# Schematic_Open-Book.net
KiCad netlist of a schematic drawn in EAGLE
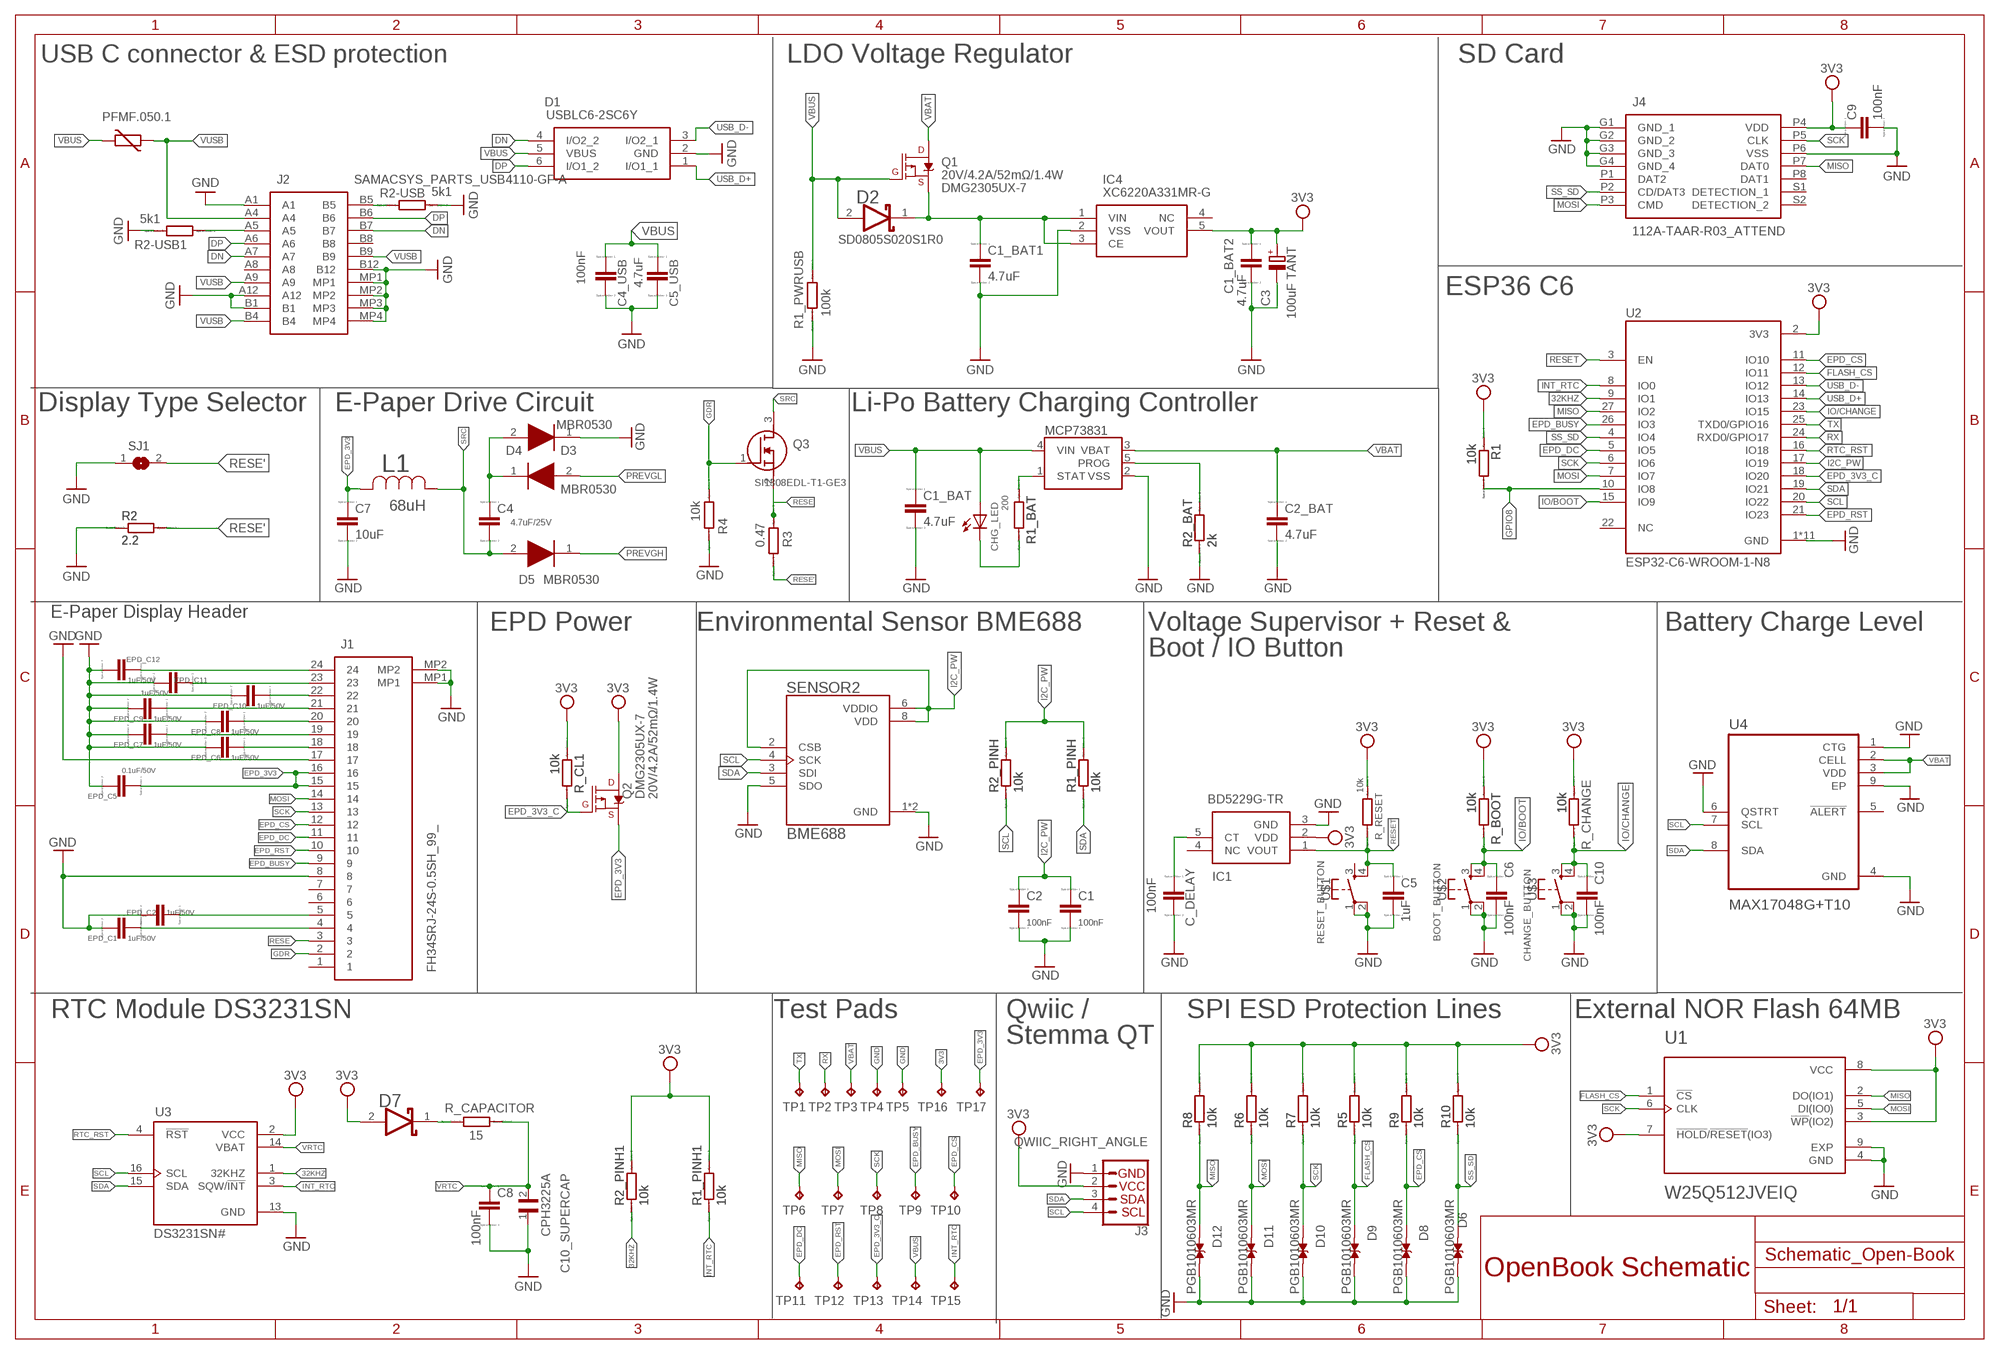
[diagram p0: schematic, sheet 1]

(export (version "E")
  (design (tool "Eeschema 10.0.6"))
  (components
    (comp (ref "C1")
      (value "100nF")
      (footprint "eagle-import:ESP32_WROVER_EAGLE-LTSPICE_C0402")
      (libsource (lib "eagle-import") (part "ESP32_WROVER_EAGLE-LTSPICE_CC0402"))
    )
    (comp (ref "C1_BAT")
      (value "4.7uF")
      (footprint "eagle-import:ESP32_WROVER_EAGLE-LTSPICE_C0402")
      (libsource (lib "eagle-import") (part "ESP32_WROVER_EAGLE-LTSPICE_CC0402"))
    )
    (comp (ref "C1_BAT1")
      (value "4.7uF")
      (footprint "eagle-import:ESP32_WROVER_EAGLE-LTSPICE_C0402")
      (libsource (lib "eagle-import") (part "ESP32_WROVER_EAGLE-LTSPICE_CC0402"))
    )
    (comp (ref "C1_BAT2")
      (value "4.7uF")
      (footprint "eagle-import:ESP32_WROVER_EAGLE-LTSPICE_C0402")
      (libsource (lib "eagle-import") (part "ESP32_WROVER_EAGLE-LTSPICE_CC0402"))
    )
    (comp (ref "C2")
      (value "100nF")
      (footprint "eagle-import:ESP32_WROVER_EAGLE-LTSPICE_C0402")
      (libsource (lib "eagle-import") (part "ESP32_WROVER_EAGLE-LTSPICE_CC0402"))
    )
    (comp (ref "C2_BAT")
      (value "4.7uF")
      (footprint "eagle-import:ESP32_WROVER_EAGLE-LTSPICE_C0402")
      (libsource (lib "eagle-import") (part "ESP32_WROVER_EAGLE-LTSPICE_CC0402"))
    )
    (comp (ref "C3")
      (value "100uF TANT")
      (footprint "eagle-import:RCL_CT3528")
      (libsource (lib "eagle-import") (part "RCL_CPOL-EUCT3528"))
    )
    (comp (ref "C4")
      (value "4.7uF/25V")
      (footprint "eagle-import:ESP32_WROVER_EAGLE-LTSPICE_C0402")
      (libsource (lib "eagle-import") (part "ESP32_WROVER_EAGLE-LTSPICE_CC0402"))
    )
    (comp (ref "C4_USB")
      (value "100nF")
      (footprint "eagle-import:EAGLE-LTSPICE_C0402")
      (libsource (lib "eagle-import") (part "EAGLE-LTSPICE_CC0402"))
    )
    (comp (ref "C5")
      (value "1uF")
      (footprint "eagle-import:ESP32_WROVER_EAGLE-LTSPICE_C0402")
      (libsource (lib "eagle-import") (part "ESP32_WROVER_EAGLE-LTSPICE_CC0402"))
    )
    (comp (ref "C5_USB")
      (value "4.7uF")
      (footprint "eagle-import:EAGLE-LTSPICE_C0402")
      (libsource (lib "eagle-import") (part "EAGLE-LTSPICE_CC0402"))
    )
    (comp (ref "C6")
      (value "100nF")
      (footprint "eagle-import:ESP32_WROVER_EAGLE-LTSPICE_C0402")
      (libsource (lib "eagle-import") (part "ESP32_WROVER_EAGLE-LTSPICE_CC0402"))
    )
    (comp (ref "C7")
      (value "10uF")
      (footprint "eagle-import:ESP32_WROVER_EAGLE-LTSPICE_C0402")
      (libsource (lib "eagle-import") (part "ESP32_WROVER_EAGLE-LTSPICE_CC0402"))
    )
    (comp (ref "C8")
      (value "100nF")
      (footprint "eagle-import:ESP32_WROVER_EAGLE-LTSPICE_C0402")
      (libsource (lib "eagle-import") (part "ESP32_WROVER_EAGLE-LTSPICE_CC0402"))
    )
    (comp (ref "C9")
      (value "100nF")
      (footprint "eagle-import:ESP32_WROVER_EAGLE-LTSPICE_C0402")
      (libsource (lib "eagle-import") (part "ESP32_WROVER_EAGLE-LTSPICE_CC0402"))
    )
    (comp (ref "C10")
      (value "100nF")
      (footprint "eagle-import:ESP32_WROVER_EAGLE-LTSPICE_C0402")
      (libsource (lib "eagle-import") (part "ESP32_WROVER_EAGLE-LTSPICE_CC0402"))
    )
    (comp (ref "C10_SUPERCAP")
      (value "CPH3225A")
      (footprint "eagle-import:CAPCP3225X100N")
      (fields (field (name "MF") "Seiko Instruments"))
      (libsource (lib "eagle-import") (part "CPH3225A"))
    )
    (comp (ref "CHG_LED")
      (value "ADAFRUIT_LEDCHIP-LED0603")
      (footprint "eagle-import:ADAFRUIT_CHIP-LED0603")
      (libsource (lib "eagle-import") (part "ADAFRUIT_LEDCHIP-LED0603"))
    )
    (comp (ref "C_DELAY")
      (value "100nF")
      (footprint "eagle-import:ESP32_WROVER_EAGLE-LTSPICE_C0402")
      (libsource (lib "eagle-import") (part "ESP32_WROVER_EAGLE-LTSPICE_CC0402"))
    )
    (comp (ref "D1")
      (value "USBLC6-2SC6Y")
      (footprint "eagle-import:SOT95P280X145-6N")
      (fields (field (name "MF") "STMicroelectronics"))
      (libsource (lib "eagle-import") (part "USBLC6-2SC6Y"))
    )
    (comp (ref "D2")
      (value "ESP32_WROVER_AVX---SD0805S020S1R0_AVX_SD0805S020S1R0_0_0AVX_SD0805S020S1R0_0_0")
      (footprint "eagle-import:ESP32_WROVER_AVX---SD0805S020S1R0_AVX_SD0805S020S1R0_0")
      (fields
        (field (name "DIGIKEY_PART_NUMBER") "478-7800-1-ND")
        (field (name "MF") "AVX")
        (field (name "MOUSER_PART_NUMBER") "581-SD0805S020S1R0")
      )
      (libsource (lib "eagle-import") (part "ESP32_WROVER_AVX---SD0805S020S1R0_AVX_SD0805S020S1R0_0_0AVX_SD0805S020S1R0_0_0"))
    )
    (comp (ref "D3")
      (value "MBR0530")
      (footprint "eagle-import:SOD3716X135N")
      (fields (field (name "MF") "ON Semiconductor"))
      (libsource (lib "eagle-import") (part "MBR0530"))
    )
    (comp (ref "D4")
      (value "MBR0530")
      (footprint "eagle-import:SOD3716X135N")
      (fields (field (name "MF") "ON Semiconductor"))
      (libsource (lib "eagle-import") (part "MBR0530"))
    )
    (comp (ref "D5")
      (value "MBR0530")
      (footprint "eagle-import:SOD3716X135N")
      (fields (field (name "MF") "ON Semiconductor"))
      (libsource (lib "eagle-import") (part "MBR0530"))
    )
    (comp (ref "D6")
      (value "PGB1010603MR")
      (footprint "eagle-import:DIOC1608X36N")
      (fields (field (name "MF") "Littelfuse Inc."))
      (libsource (lib "eagle-import") (part "PGB1010603MR"))
    )
    (comp (ref "D7")
      (value "ESP32_WROVER_AVX---SD0805S020S1R0_AVX_SD0805S020S1R0_0_0AVX_SD0805S020S1R0_0_0")
      (footprint "eagle-import:ESP32_WROVER_AVX---SD0805S020S1R0_AVX_SD0805S020S1R0_0")
      (fields
        (field (name "DIGIKEY_PART_NUMBER") "478-7800-1-ND")
        (field (name "MF") "AVX")
        (field (name "MOUSER_PART_NUMBER") "581-SD0805S020S1R0")
      )
      (libsource (lib "eagle-import") (part "ESP32_WROVER_AVX---SD0805S020S1R0_AVX_SD0805S020S1R0_0_0AVX_SD0805S020S1R0_0_0"))
    )
    (comp (ref "D8")
      (value "PGB1010603MR")
      (footprint "eagle-import:DIOC1608X36N")
      (fields (field (name "MF") "Littelfuse Inc."))
      (libsource (lib "eagle-import") (part "PGB1010603MR"))
    )
    (comp (ref "D9")
      (value "PGB1010603MR")
      (footprint "eagle-import:DIOC1608X36N")
      (fields (field (name "MF") "Littelfuse Inc."))
      (libsource (lib "eagle-import") (part "PGB1010603MR"))
    )
    (comp (ref "D10")
      (value "PGB1010603MR")
      (footprint "eagle-import:DIOC1608X36N")
      (fields (field (name "MF") "Littelfuse Inc."))
      (libsource (lib "eagle-import") (part "PGB1010603MR"))
    )
    (comp (ref "D11")
      (value "PGB1010603MR")
      (footprint "eagle-import:DIOC1608X36N")
      (fields (field (name "MF") "Littelfuse Inc."))
      (libsource (lib "eagle-import") (part "PGB1010603MR"))
    )
    (comp (ref "D12")
      (value "PGB1010603MR")
      (footprint "eagle-import:DIOC1608X36N")
      (fields (field (name "MF") "Littelfuse Inc."))
      (libsource (lib "eagle-import") (part "PGB1010603MR"))
    )
    (comp (ref "EPD_C1")
      (value "1uF/50V")
      (footprint "eagle-import:ESP32_WROVER_EAGLE-LTSPICE_C0402")
      (libsource (lib "eagle-import") (part "ESP32_WROVER_EAGLE-LTSPICE_CC0402"))
    )
    (comp (ref "EPD_C2")
      (value "1uF/50V")
      (footprint "eagle-import:ESP32_WROVER_EAGLE-LTSPICE_C0402")
      (libsource (lib "eagle-import") (part "ESP32_WROVER_EAGLE-LTSPICE_CC0402"))
    )
    (comp (ref "EPD_C5")
      (value "0.1uF/50V")
      (footprint "eagle-import:EAGLE-LTSPICE_C0402")
      (libsource (lib "eagle-import") (part "EAGLE-LTSPICE_CC0402"))
    )
    (comp (ref "EPD_C6")
      (value "1uF/50V")
      (footprint "eagle-import:EAGLE-LTSPICE_C0402")
      (libsource (lib "eagle-import") (part "EAGLE-LTSPICE_CC0402"))
    )
    (comp (ref "EPD_C7")
      (value "1uF/50V")
      (footprint "eagle-import:EAGLE-LTSPICE_C0402")
      (libsource (lib "eagle-import") (part "EAGLE-LTSPICE_CC0402"))
    )
    (comp (ref "EPD_C8")
      (value "1uF/50V")
      (footprint "eagle-import:EAGLE-LTSPICE_C0402")
      (libsource (lib "eagle-import") (part "EAGLE-LTSPICE_CC0402"))
    )
    (comp (ref "EPD_C9")
      (value "1uF/50V")
      (footprint "eagle-import:EAGLE-LTSPICE_C0402")
      (libsource (lib "eagle-import") (part "EAGLE-LTSPICE_CC0402"))
    )
    (comp (ref "EPD_C10")
      (value "1uF/50V")
      (footprint "eagle-import:EAGLE-LTSPICE_C0402")
      (libsource (lib "eagle-import") (part "EAGLE-LTSPICE_CC0402"))
    )
    (comp (ref "EPD_C11")
      (value "1uF/50V")
      (footprint "eagle-import:EAGLE-LTSPICE_C0402")
      (libsource (lib "eagle-import") (part "EAGLE-LTSPICE_CC0402"))
    )
    (comp (ref "EPD_C12")
      (value "1uF/50V")
      (footprint "eagle-import:EAGLE-LTSPICE_C0402")
      (libsource (lib "eagle-import") (part "EAGLE-LTSPICE_CC0402"))
    )
    (comp (ref "IC1")
      (value "BD5229G-TR")
      (footprint "eagle-import:SOT95P280X125-5N")
      (fields (field (name "MOUSER_PART_NUMBER") "755-BD5229G-TR"))
      (libsource (lib "eagle-import") (part "BD5229G-TR"))
    )
    (comp (ref "IC4")
      (value "XC6220A331MR-G")
      (footprint "eagle-import:SOT95P280X120-5N")
      (fields (field (name "MOUSER_PART_NUMBER") "865-XC6220A331MR-G"))
      (libsource (lib "eagle-import") (part "XC6220A331MR-G"))
    )
    (comp (ref "J1")
      (value "FH34SRJ-24S-0.5SH_99_")
      (footprint "eagle-import:FH34SRJ24S05SH99")
      (fields
        (field (name "MANUFACTURER_PART_NUMBER") "FH34SRJ-24S-0.5SH(99)")
        (field (name "MOUSER_PART_NUMBER") "798-FH34SRJ24S05SH99")
      )
      (libsource (lib "eagle-import") (part "FH34SRJ-24S-0.5SH_99_"))
    )
    (comp (ref "J2")
      (value "SAMACSYS_PARTS_USB4110-GF-A")
      (footprint "eagle-import:SAMACSYS_PARTS_USB4110GFA")
      (fields
        (field (name "MANUFACTURER_PART_NUMBER") "USB4110-GF-A")
        (field (name "MOUSER_PART_NUMBER") "640-USB4110-GF-A")
      )
      (libsource (lib "eagle-import") (part "SAMACSYS_PARTS_USB4110-GF-A"))
    )
    (comp (ref "J3")
      (value "QWIIC_RIGHT_ANGLE")
      (footprint "eagle-import:JST04_1MM_RA")
      (libsource (lib "eagle-import") (part "QWIIC_CONNECTORJS-1MM"))
    )
    (comp (ref "J4")
      (value "112A-TAAR-R03_ATTEND")
      (footprint "eagle-import:112ATAARR03ATTEND")
      (fields (field (name "MANUFACTURER_PART_NUMBER") "112A-TAAR-R03 ATTEND"))
      (libsource (lib "eagle-import") (part "112A-TAAR-R03_ATTEND"))
    )
    (comp (ref "L1")
      (value "68uH")
      (footprint "eagle-import:IND_4828-WE-TPC_WRE")
      (fields
        (field (name "MANUFACTURER_PART_NUMBER") "744043680")
        (field (name "COPYRIGHT") "Copyright (C) 2024 Ultra Librarian. All rights reserved.")
      )
      (libsource (lib "eagle-import") (part "744043680IND_4828-WE-TPC_WRE"))
    )
    (comp (ref "MCP73831")
      (value "ESP32_WROVER_SPARKFUN-IC-POWER_MCP73831")
      (footprint "eagle-import:ESP32_WROVER_SPARKFUN-IC-POWER_SOT23-5")
      (libsource (lib "eagle-import") (part "ESP32_WROVER_SPARKFUN-IC-POWER_MCP73831"))
    )
    (comp (ref "PFMF.050.1")
      (value "ESP32C6_VARISTORCN1812")
      (footprint "eagle-import:ESP32C6_VARISTOR_CT_CN1812")
      (libsource (lib "eagle-import") (part "ESP32C6_VARISTORCN1812"))
    )
    (comp (ref "Q1")
      (value "20V/4.2A/52mΩ/1.4W")
      (footprint "eagle-import:ESP32_WROVER_SPARKFUN-DISCRETESEMI_SOT23-3")
      (libsource (lib "eagle-import") (part "ESP32_WROVER_SPARKFUN-DISCRETESEMI_MOSFET_PCH-DMG2305UX-7"))
    )
    (comp (ref "Q2")
      (value "20V/4.2A/52mΩ/1.4W")
      (footprint "eagle-import:ESP32_WROVER_SPARKFUN-DISCRETESEMI_SOT23-3")
      (libsource (lib "eagle-import") (part "ESP32_WROVER_SPARKFUN-DISCRETESEMI_MOSFET_PCH-DMG2305UX-7"))
    )
    (comp (ref "Q3")
      (value "SI1308EDL-T1-GE3")
      (footprint "eagle-import:SOT65P210X110-3N")
      (fields (field (name "MF") "Vishay Siliconix"))
      (libsource (lib "eagle-import") (part "SI1308EDL-T1-GE3"))
    )
    (comp (ref "R1")
      (value "10k")
      (footprint "eagle-import:ESP32_WROVER_EAGLE-LTSPICE_R0402")
      (libsource (lib "eagle-import") (part "ESP32_WROVER_EAGLE-LTSPICE_RR0402"))
    )
    (comp (ref "R1_BAT")
      (value "200")
      (footprint "eagle-import:ESP32_WROVER_EAGLE-LTSPICE_R0402")
      (libsource (lib "eagle-import") (part "ESP32_WROVER_EAGLE-LTSPICE_RR0402"))
    )
    (comp (ref "R1_PINH")
      (value "10k")
      (footprint "eagle-import:ESP32_WROVER_EAGLE-LTSPICE_R0402")
      (libsource (lib "eagle-import") (part "ESP32_WROVER_EAGLE-LTSPICE_RR0402"))
    )
    (comp (ref "R1_PINH1")
      (value "10k")
      (footprint "eagle-import:ESP32_WROVER_EAGLE-LTSPICE_R0402")
      (libsource (lib "eagle-import") (part "ESP32_WROVER_EAGLE-LTSPICE_RR0402"))
    )
    (comp (ref "R1_PWRUSB")
      (value "100k")
      (footprint "eagle-import:ESP32_WROVER_EAGLE-LTSPICE_R0402")
      (libsource (lib "eagle-import") (part "ESP32_WROVER_EAGLE-LTSPICE_RR0402"))
    )
    (comp (ref "R2")
      (value "2.2")
      (footprint "eagle-import:ESP32_WROVER_EAGLE-LTSPICE_R0402")
      (libsource (lib "eagle-import") (part "ESP32_WROVER_EAGLE-LTSPICE_RR0402"))
    )
    (comp (ref "R2-USB")
      (value "5k1")
      (footprint "eagle-import:ESP32_WROVER_EAGLE-LTSPICE_R0402")
      (libsource (lib "eagle-import") (part "ESP32_WROVER_EAGLE-LTSPICE_RR0402"))
    )
    (comp (ref "R2-USB1")
      (value "5k1")
      (footprint "eagle-import:ESP32_WROVER_EAGLE-LTSPICE_R0402")
      (libsource (lib "eagle-import") (part "ESP32_WROVER_EAGLE-LTSPICE_RR0402"))
    )
    (comp (ref "R2_BAT")
      (value "2k")
      (footprint "eagle-import:ESP32_WROVER_EAGLE-LTSPICE_R0402")
      (libsource (lib "eagle-import") (part "ESP32_WROVER_EAGLE-LTSPICE_RR0402"))
    )
    (comp (ref "R2_PINH")
      (value "10k")
      (footprint "eagle-import:ESP32_WROVER_EAGLE-LTSPICE_R0402")
      (libsource (lib "eagle-import") (part "ESP32_WROVER_EAGLE-LTSPICE_RR0402"))
    )
    (comp (ref "R2_PINH1")
      (value "10k")
      (footprint "eagle-import:ESP32_WROVER_EAGLE-LTSPICE_R0402")
      (libsource (lib "eagle-import") (part "ESP32_WROVER_EAGLE-LTSPICE_RR0402"))
    )
    (comp (ref "R3")
      (value "0.47")
      (footprint "eagle-import:ESP32_WROVER_EAGLE-LTSPICE_R0402")
      (libsource (lib "eagle-import") (part "ESP32_WROVER_EAGLE-LTSPICE_RR0402"))
    )
    (comp (ref "R4")
      (value "10k")
      (footprint "eagle-import:ESP32_WROVER_EAGLE-LTSPICE_R0402")
      (libsource (lib "eagle-import") (part "ESP32_WROVER_EAGLE-LTSPICE_RR0402"))
    )
    (comp (ref "R5")
      (value "10k")
      (footprint "eagle-import:ESP32_WROVER_EAGLE-LTSPICE_R0402")
      (libsource (lib "eagle-import") (part "ESP32_WROVER_EAGLE-LTSPICE_RR0402"))
    )
    (comp (ref "R6")
      (value "10k")
      (footprint "eagle-import:ESP32_WROVER_EAGLE-LTSPICE_R0402")
      (libsource (lib "eagle-import") (part "ESP32_WROVER_EAGLE-LTSPICE_RR0402"))
    )
    (comp (ref "R7")
      (value "10k")
      (footprint "eagle-import:ESP32_WROVER_EAGLE-LTSPICE_R0402")
      (libsource (lib "eagle-import") (part "ESP32_WROVER_EAGLE-LTSPICE_RR0402"))
    )
    (comp (ref "R8")
      (value "10k")
      (footprint "eagle-import:ESP32_WROVER_EAGLE-LTSPICE_R0402")
      (libsource (lib "eagle-import") (part "ESP32_WROVER_EAGLE-LTSPICE_RR0402"))
    )
    (comp (ref "R9")
      (value "10k")
      (footprint "eagle-import:ESP32_WROVER_EAGLE-LTSPICE_R0402")
      (libsource (lib "eagle-import") (part "ESP32_WROVER_EAGLE-LTSPICE_RR0402"))
    )
    (comp (ref "R10")
      (value "10k")
      (footprint "eagle-import:ESP32_WROVER_EAGLE-LTSPICE_R0402")
      (libsource (lib "eagle-import") (part "ESP32_WROVER_EAGLE-LTSPICE_RR0402"))
    )
    (comp (ref "R_BOOT")
      (value "10k")
      (footprint "eagle-import:ESP32_WROVER_EAGLE-LTSPICE_R0402")
      (libsource (lib "eagle-import") (part "ESP32_WROVER_EAGLE-LTSPICE_RR0402"))
    )
    (comp (ref "R_CAPACITOR")
      (value "15")
      (footprint "eagle-import:ESP32_WROVER_EAGLE-LTSPICE_R0402")
      (libsource (lib "eagle-import") (part "ESP32_WROVER_EAGLE-LTSPICE_RR0402"))
    )
    (comp (ref "R_CHANGE")
      (value "10k")
      (footprint "eagle-import:ESP32_WROVER_EAGLE-LTSPICE_R0402")
      (libsource (lib "eagle-import") (part "ESP32_WROVER_EAGLE-LTSPICE_RR0402"))
    )
    (comp (ref "R_CL1")
      (value "10k")
      (footprint "eagle-import:ESP32_WROVER_EAGLE-LTSPICE_R0402")
      (libsource (lib "eagle-import") (part "ESP32_WROVER_EAGLE-LTSPICE_RR0402"))
    )
    (comp (ref "R_RESET")
      (value "10k")
      (footprint "eagle-import:ESP32_WROVER_EAGLE-LTSPICE_R0402")
      (libsource (lib "eagle-import") (part "ESP32_WROVER_EAGLE-LTSPICE_RR0402"))
    )
    (comp (ref "SENSOR2")
      (value "BME688")
      (footprint "eagle-import:ESP32_WROVER_BME680_PSON80P300X300X100-8N")
      (fields (field (name "MF") "Bosch Sensortec") (field (name "MP") "BME680"))
      (libsource (lib "eagle-import") (part "ESP32_WROVER_BME680_BME680"))
    )
    (comp (ref "SJ1") (value "SJ") (footprint "eagle-import:SJ") (libsource (lib "eagle-import") (part "SJ")))
    (comp (ref "TP1")
      (value "TPTP20R")
      (footprint "eagle-import:TP20R")
      (libsource (lib "eagle-import") (part "TPTP20R"))
    )
    (comp (ref "TP2")
      (value "TPTP20R")
      (footprint "eagle-import:TP20R")
      (libsource (lib "eagle-import") (part "TPTP20R"))
    )
    (comp (ref "TP3")
      (value "TPTP20R")
      (footprint "eagle-import:TP20R")
      (libsource (lib "eagle-import") (part "TPTP20R"))
    )
    (comp (ref "TP4")
      (value "TPTP20R")
      (footprint "eagle-import:TP20R")
      (libsource (lib "eagle-import") (part "TPTP20R"))
    )
    (comp (ref "TP5")
      (value "TPTP20R")
      (footprint "eagle-import:TP20R")
      (libsource (lib "eagle-import") (part "TPTP20R"))
    )
    (comp (ref "TP6")
      (value "TPTP20R")
      (footprint "eagle-import:TP20R")
      (libsource (lib "eagle-import") (part "TPTP20R"))
    )
    (comp (ref "TP7")
      (value "TPTP20R")
      (footprint "eagle-import:TP20R")
      (libsource (lib "eagle-import") (part "TPTP20R"))
    )
    (comp (ref "TP8")
      (value "TPTP20R")
      (footprint "eagle-import:TP20R")
      (libsource (lib "eagle-import") (part "TPTP20R"))
    )
    (comp (ref "TP9")
      (value "TPTP20R")
      (footprint "eagle-import:TP20R")
      (libsource (lib "eagle-import") (part "TPTP20R"))
    )
    (comp (ref "TP10")
      (value "TPTP20R")
      (footprint "eagle-import:TP20R")
      (libsource (lib "eagle-import") (part "TPTP20R"))
    )
    (comp (ref "TP11")
      (value "TPTP20R")
      (footprint "eagle-import:TP20R")
      (libsource (lib "eagle-import") (part "TPTP20R"))
    )
    (comp (ref "TP12")
      (value "TPTP20R")
      (footprint "eagle-import:TP20R")
      (libsource (lib "eagle-import") (part "TPTP20R"))
    )
    (comp (ref "TP13")
      (value "TPTP20R")
      (footprint "eagle-import:TP20R")
      (libsource (lib "eagle-import") (part "TPTP20R"))
    )
    (comp (ref "TP14")
      (value "TPTP20R")
      (footprint "eagle-import:TP20R")
      (libsource (lib "eagle-import") (part "TPTP20R"))
    )
    (comp (ref "TP15")
      (value "TPTP20R")
      (footprint "eagle-import:TP20R")
      (libsource (lib "eagle-import") (part "TPTP20R"))
    )
    (comp (ref "TP16")
      (value "TPTP20R")
      (footprint "eagle-import:TP20R")
      (libsource (lib "eagle-import") (part "TPTP20R"))
    )
    (comp (ref "TP17")
      (value "TPTP20R")
      (footprint "eagle-import:TP20R")
      (libsource (lib "eagle-import") (part "TPTP20R"))
    )
    (comp (ref "U$1")
      (value "RESET_BUTTON")
      (footprint "eagle-import:MYBUTTON")
      (libsource (lib "eagle-import") (part "BUTTON_CUSYOMV1"))
    )
    (comp (ref "U$2")
      (value "BOOT_BUTTON")
      (footprint "eagle-import:MYBUTTON")
      (libsource (lib "eagle-import") (part "BUTTON_CUSYOMV1"))
    )
    (comp (ref "U$3")
      (value "CHANGE_BUTTON")
      (footprint "eagle-import:MYBUTTON")
      (libsource (lib "eagle-import") (part "BUTTON_CUSYOMV1"))
    )
    (comp (ref "U1")
      (value "W25Q512JVEIQ")
      (footprint "eagle-import:SON127P600X800X80-9N")
      (fields (field (name "MF") "Winbond Electronics"))
      (libsource (lib "eagle-import") (part "W25Q512JVEIQ"))
    )
    (comp (ref "U2")
      (value "ESP32-C6-WROOM-1-N8")
      (footprint "eagle-import:XCVR_ESP32-C6-WROOM-1-N8")
      (fields (field (name "MF") "Espressif Systems"))
      (libsource (lib "eagle-import") (part "ESP32-C6-WROOM-1-N8"))
    )
    (comp (ref "U3")
      (value "DS3231SN#")
      (footprint "eagle-import:SOIC127P1032X265-16N")
      (fields (field (name "MF") "Analog Devices"))
      (libsource (lib "eagle-import") (part "DS3231SN#"))
    )
    (comp (ref "U4")
      (value "MAX17048G+T10")
      (footprint "eagle-import:SON50P200X200X80-9N")
      (fields (field (name "MF") "Analog Devices"))
      (libsource (lib "eagle-import") (part "MAX17048G+T10"))
    )
  )
  (nets
    (net (code "1") (name "3V3") (class "Default")
      (node (ref "C1_BAT2") (pin "1") (pinfunction "1_1") (pintype "passive"))
      (node (ref "C3") (pin "+") (pinfunction "+_+") (pintype "passive"))
      (node (ref "C9") (pin "1") (pinfunction "1_1") (pintype "passive"))
      (node (ref "D7") (pin "2") (pinfunction "ANODE_2") (pintype "bidirectional"))
      (node (ref "IC1") (pin "2") (pinfunction "VDD_2") (pintype "bidirectional"))
      (node (ref "IC4") (pin "5") (pinfunction "VOUT_5") (pintype "bidirectional"))
      (node (ref "J3") (pin "2") (pinfunction "2_2") (pintype "power_in"))
      (node (ref "J4") (pin "P4") (pinfunction "VDD_P4") (pintype "bidirectional"))
      (node (ref "Q2") (pin "3") (pinfunction "D_3") (pintype "bidirectional"))
      (node (ref "R1") (pin "1") (pinfunction "1_1") (pintype "passive"))
      (node (ref "R10") (pin "2") (pinfunction "2_2") (pintype "passive"))
      (node (ref "R1_PINH1") (pin "2") (pinfunction "2_2") (pintype "passive"))
      (node (ref "R2_PINH1") (pin "2") (pinfunction "2_2") (pintype "passive"))
      (node (ref "R5") (pin "2") (pinfunction "2_2") (pintype "passive"))
      (node (ref "R6") (pin "2") (pinfunction "2_2") (pintype "passive"))
      (node (ref "R7") (pin "2") (pinfunction "2_2") (pintype "passive"))
      (node (ref "R8") (pin "2") (pinfunction "2_2") (pintype "passive"))
      (node (ref "R9") (pin "2") (pinfunction "2_2") (pintype "passive"))
      (node (ref "R_BOOT") (pin "1") (pinfunction "1_1") (pintype "passive"))
      (node (ref "R_CHANGE") (pin "1") (pinfunction "1_1") (pintype "passive"))
      (node (ref "R_CL1") (pin "1") (pinfunction "1_1") (pintype "passive"))
      (node (ref "R_RESET") (pin "1") (pinfunction "1_1") (pintype "passive"))
      (node (ref "TP16") (pin "TP") (pinfunction "TP_TP") (pintype "input"))
      (node (ref "U1") (pin "3") (pinfunction "~{WP}(IO2)_3") (pintype "bidirectional"))
      (node (ref "U1") (pin "7") (pinfunction "~{HOLD}/~{RESET}(IO3)_7") (pintype "bidirectional"))
      (node (ref "U1") (pin "8") (pinfunction "VCC_8") (pintype "power_in"))
      (node (ref "U2") (pin "2") (pinfunction "3V3_2") (pintype "power_in"))
      (node (ref "U3") (pin "2") (pinfunction "VCC_2") (pintype "power_in"))
    )
    (net (code "2") (name "32KHZ") (class "Default")
      (node (ref "R2_PINH1") (pin "1") (pinfunction "1_1") (pintype "passive"))
      (node (ref "U2") (pin "9") (pinfunction "IO1_9") (pintype "bidirectional"))
      (node (ref "U3") (pin "1") (pinfunction "32KHZ_1") (pintype "output"))
    )
    (net (code "3") (name "DN") (class "Default")
      (node (ref "D1") (pin "4") (pinfunction "I/O2_2_4") (pintype "bidirectional"))
      (node (ref "J2") (pin "A7") (pinfunction "A7_A7") (pintype "bidirectional"))
      (node (ref "J2") (pin "B7") (pinfunction "B7_B7") (pintype "bidirectional"))
    )
    (net (code "4") (name "DP") (class "Default")
      (node (ref "D1") (pin "6") (pinfunction "I/O1_2_6") (pintype "bidirectional"))
      (node (ref "J2") (pin "A6") (pinfunction "A6_A6") (pintype "bidirectional"))
      (node (ref "J2") (pin "B6") (pinfunction "B6_B6") (pintype "bidirectional"))
    )
    (net (code "5") (name "EPD_3V3") (class "Default")
      (node (ref "C7") (pin "1") (pinfunction "1_1") (pintype "passive"))
      (node (ref "EPD_C5") (pin "1") (pinfunction "1_1") (pintype "passive"))
      (node (ref "J1") (pin "15") (pinfunction "15_15") (pintype "bidirectional"))
      (node (ref "J1") (pin "16") (pinfunction "16_16") (pintype "bidirectional"))
      (node (ref "L1") (pin "2") (pinfunction "2_2") (pintype "passive"))
      (node (ref "Q2") (pin "2") (pinfunction "S_2") (pintype "bidirectional"))
      (node (ref "TP17") (pin "TP") (pinfunction "TP_TP") (pintype "input"))
    )
    (net (code "6") (name "EPD_3V3_C") (class "Default")
      (node (ref "Q2") (pin "1") (pinfunction "G_1") (pintype "bidirectional"))
      (node (ref "R_CL1") (pin "2") (pinfunction "2_2") (pintype "passive"))
      (node (ref "TP13") (pin "TP") (pinfunction "TP_TP") (pintype "input"))
      (node (ref "U2") (pin "18") (pinfunction "IO20_18") (pintype "bidirectional"))
    )
    (net (code "7") (name "EPD_BUSY") (class "Default")
      (node (ref "J1") (pin "9") (pinfunction "9_9") (pintype "bidirectional"))
      (node (ref "TP9") (pin "TP") (pinfunction "TP_TP") (pintype "input"))
      (node (ref "U2") (pin "26") (pinfunction "IO3_26") (pintype "bidirectional"))
    )
    (net (code "8") (name "EPD_CS") (class "Default")
      (node (ref "D8") (pin "1") (pinfunction "1_1") (pintype "passive"))
      (node (ref "J1") (pin "12") (pinfunction "12_12") (pintype "bidirectional"))
      (node (ref "R9") (pin "1") (pinfunction "1_1") (pintype "passive"))
      (node (ref "TP10") (pin "TP") (pinfunction "TP_TP") (pintype "input"))
      (node (ref "U2") (pin "11") (pinfunction "IO10_11") (pintype "bidirectional"))
    )
    (net (code "9") (name "EPD_DC") (class "Default")
      (node (ref "J1") (pin "11") (pinfunction "11_11") (pintype "bidirectional"))
      (node (ref "TP11") (pin "TP") (pinfunction "TP_TP") (pintype "input"))
      (node (ref "U2") (pin "5") (pinfunction "IO5_5") (pintype "bidirectional"))
    )
    (net (code "10") (name "EPD_RST") (class "Default")
      (node (ref "J1") (pin "10") (pinfunction "10_10") (pintype "bidirectional"))
      (node (ref "TP12") (pin "TP") (pinfunction "TP_TP") (pintype "input"))
      (node (ref "U2") (pin "21") (pinfunction "IO23_21") (pintype "bidirectional"))
    )
    (net (code "11") (name "FLASH_CS") (class "Default")
      (node (ref "D9") (pin "1") (pinfunction "1_1") (pintype "passive"))
      (node (ref "R5") (pin "1") (pinfunction "1_1") (pintype "passive"))
      (node (ref "U1") (pin "1") (pinfunction "~{CS}_1") (pintype "input"))
      (node (ref "U2") (pin "12") (pinfunction "IO11_12") (pintype "bidirectional"))
    )
    (net (code "12") (name "GDR") (class "Default")
      (node (ref "J1") (pin "2") (pinfunction "2_2") (pintype "bidirectional"))
      (node (ref "Q3") (pin "1") (pinfunction "G_1") (pintype "bidirectional"))
      (node (ref "R4") (pin "2") (pinfunction "2_2") (pintype "passive"))
    )
    (net (code "13") (name "GND") (class "Default")
      (node (ref "C1") (pin "2") (pinfunction "2_2") (pintype "passive"))
      (node (ref "C10") (pin "2") (pinfunction "2_2") (pintype "passive"))
      (node (ref "C10_SUPERCAP") (pin "1") (pinfunction "1_1") (pintype "passive"))
      (node (ref "C1_BAT") (pin "2") (pinfunction "2_2") (pintype "passive"))
      (node (ref "C1_BAT1") (pin "2") (pinfunction "2_2") (pintype "passive"))
      (node (ref "C1_BAT2") (pin "2") (pinfunction "2_2") (pintype "passive"))
      (node (ref "C2") (pin "2") (pinfunction "2_2") (pintype "passive"))
      (node (ref "C2_BAT") (pin "2") (pinfunction "2_2") (pintype "passive"))
      (node (ref "C3") (pin "-") (pinfunction "-_-") (pintype "passive"))
      (node (ref "C4_USB") (pin "2") (pinfunction "2_2") (pintype "passive"))
      (node (ref "C5") (pin "2") (pinfunction "2_2") (pintype "passive"))
      (node (ref "C5_USB") (pin "2") (pinfunction "2_2") (pintype "passive"))
      (node (ref "C6") (pin "2") (pinfunction "2_2") (pintype "passive"))
      (node (ref "C7") (pin "2") (pinfunction "2_2") (pintype "passive"))
      (node (ref "C8") (pin "2") (pinfunction "2_2") (pintype "passive"))
      (node (ref "C9") (pin "2") (pinfunction "2_2") (pintype "passive"))
      (node (ref "C_DELAY") (pin "2") (pinfunction "2_2") (pintype "passive"))
      (node (ref "D1") (pin "2") (pinfunction "GND_2") (pintype "bidirectional"))
      (node (ref "D10") (pin "2") (pinfunction "2_2") (pintype "passive"))
      (node (ref "D11") (pin "2") (pinfunction "2_2") (pintype "passive"))
      (node (ref "D12") (pin "2") (pinfunction "2_2") (pintype "passive"))
      (node (ref "D4") (pin "1") (pinfunction "K_1") (pintype "bidirectional"))
      (node (ref "D6") (pin "2") (pinfunction "2_2") (pintype "passive"))
      (node (ref "D8") (pin "2") (pinfunction "2_2") (pintype "passive"))
      (node (ref "D9") (pin "2") (pinfunction "2_2") (pintype "passive"))
      (node (ref "EPD_C1") (pin "2") (pinfunction "2_2") (pintype "passive"))
      (node (ref "EPD_C10") (pin "2") (pinfunction "2_2") (pintype "passive"))
      (node (ref "EPD_C11") (pin "2") (pinfunction "2_2") (pintype "passive"))
      (node (ref "EPD_C12") (pin "2") (pinfunction "2_2") (pintype "passive"))
      (node (ref "EPD_C2") (pin "2") (pinfunction "2_2") (pintype "passive"))
      (node (ref "EPD_C5") (pin "2") (pinfunction "2_2") (pintype "passive"))
      (node (ref "EPD_C6") (pin "2") (pinfunction "2_2") (pintype "passive"))
      (node (ref "EPD_C7") (pin "2") (pinfunction "2_2") (pintype "passive"))
      (node (ref "EPD_C8") (pin "2") (pinfunction "2_2") (pintype "passive"))
      (node (ref "EPD_C9") (pin "2") (pinfunction "2_2") (pintype "passive"))
      (node (ref "IC1") (pin "3") (pinfunction "GND_3") (pintype "bidirectional"))
      (node (ref "IC4") (pin "2") (pinfunction "VSS_2") (pintype "bidirectional"))
      (node (ref "J1") (pin "17") (pinfunction "17_17") (pintype "bidirectional"))
      (node (ref "J1") (pin "8") (pinfunction "8_8") (pintype "bidirectional"))
      (node (ref "J1") (pin "MP1") (pinfunction "MP1_MP1") (pintype "bidirectional"))
      (node (ref "J1") (pin "MP2") (pinfunction "MP2_MP2") (pintype "bidirectional"))
      (node (ref "J2") (pin "A1") (pinfunction "A1_A1") (pintype "bidirectional"))
      (node (ref "J2") (pin "A12") (pinfunction "A12_A12") (pintype "bidirectional"))
      (node (ref "J2") (pin "B1") (pinfunction "B1_B1") (pintype "bidirectional"))
      (node (ref "J2") (pin "B12") (pinfunction "B12_B12") (pintype "bidirectional"))
      (node (ref "J2") (pin "MP1") (pinfunction "MP1_MP1") (pintype "bidirectional"))
      (node (ref "J2") (pin "MP2") (pinfunction "MP2_MP2") (pintype "bidirectional"))
      (node (ref "J2") (pin "MP3") (pinfunction "MP3_MP3") (pintype "bidirectional"))
      (node (ref "J2") (pin "MP4") (pinfunction "MP4_MP4") (pintype "bidirectional"))
      (node (ref "J3") (pin "1") (pinfunction "1_1") (pintype "power_in"))
      (node (ref "J4") (pin "G1") (pinfunction "GND_1_G1") (pintype "bidirectional"))
      (node (ref "J4") (pin "G2") (pinfunction "GND_2_G2") (pintype "bidirectional"))
      (node (ref "J4") (pin "G3") (pinfunction "GND_3_G3") (pintype "bidirectional"))
      (node (ref "J4") (pin "G4") (pinfunction "GND_4_G4") (pintype "bidirectional"))
      (node (ref "J4") (pin "P6") (pinfunction "VSS_P6") (pintype "bidirectional"))
      (node (ref "MCP73831") (pin "2") (pinfunction "VSS_2") (pintype "power_in"))
      (node (ref "R1_PWRUSB") (pin "2") (pinfunction "2_2") (pintype "passive"))
      (node (ref "R2") (pin "1") (pinfunction "1_1") (pintype "passive"))
      (node (ref "R2-USB") (pin "2") (pinfunction "2_2") (pintype "passive"))
      (node (ref "R2-USB1") (pin "1") (pinfunction "1_1") (pintype "passive"))
      (node (ref "R2_BAT") (pin "1") (pinfunction "1_1") (pintype "passive"))
      (node (ref "R4") (pin "1") (pinfunction "1_1") (pintype "passive"))
      (node (ref "SENSOR2") (pin "1") (pinfunction "GND_1") (pintype "power_in"))
      (node (ref "SENSOR2") (pin "5") (pinfunction "SDO_5") (pintype "bidirectional"))
      (node (ref "SENSOR2") (pin "7") (pinfunction "GND_7") (pintype "power_in"))
      (node (ref "SJ1") (pin "1") (pinfunction "1_1") (pintype "passive"))
      (node (ref "TP4") (pin "TP") (pinfunction "TP_TP") (pintype "input"))
      (node (ref "TP5") (pin "TP") (pinfunction "TP_TP") (pintype "input"))
      (node (ref "U$1") (pin "1") (pinfunction "1_1") (pintype "passive"))
      (node (ref "U$1") (pin "2") (pinfunction "2_2") (pintype "passive"))
      (node (ref "U$2") (pin "1") (pinfunction "1_1") (pintype "passive"))
      (node (ref "U$2") (pin "2") (pinfunction "2_2") (pintype "passive"))
      (node (ref "U$3") (pin "1") (pinfunction "1_1") (pintype "passive"))
      (node (ref "U$3") (pin "2") (pinfunction "2_2") (pintype "passive"))
      (node (ref "U1") (pin "4") (pinfunction "GND_4") (pintype "power_in"))
      (node (ref "U1") (pin "9") (pinfunction "EXP_9") (pintype "passive"))
      (node (ref "U2") (pin "1") (pinfunction "GND_1") (pintype "power_in"))
      (node (ref "U2") (pin "28") (pinfunction "GND_28") (pintype "power_in"))
      (node (ref "U2") (pin "29_1") (pinfunction "GND_29_1") (pintype "power_in"))
      (node (ref "U2") (pin "29_2") (pinfunction "GND_29_2") (pintype "power_in"))
      (node (ref "U2") (pin "29_3") (pinfunction "GND_29_3") (pintype "power_in"))
      (node (ref "U2") (pin "29_4") (pinfunction "GND_29_4") (pintype "power_in"))
      (node (ref "U2") (pin "29_5") (pinfunction "GND_29_5") (pintype "power_in"))
      (node (ref "U2") (pin "29_6") (pinfunction "GND_29_6") (pintype "power_in"))
      (node (ref "U2") (pin "29_7") (pinfunction "GND_29_7") (pintype "power_in"))
      (node (ref "U2") (pin "29_8") (pinfunction "GND_29_8") (pintype "power_in"))
      (node (ref "U2") (pin "29_9") (pinfunction "GND_29_9") (pintype "power_in"))
      (node (ref "U3") (pin "13") (pinfunction "GND_13") (pintype "power_in"))
      (node (ref "U4") (pin "1") (pinfunction "CTG_1") (pintype "power_in"))
      (node (ref "U4") (pin "4") (pinfunction "GND_4") (pintype "power_in"))
      (node (ref "U4") (pin "6") (pinfunction "QSTRT_6") (pintype "input"))
      (node (ref "U4") (pin "9") (pinfunction "EP_9") (pintype "power_in"))
    )
    (net (code "14") (name "GPIO8") (class "Default")
      (node (ref "R1") (pin "2") (pinfunction "2_2") (pintype "passive"))
      (node (ref "U2") (pin "10") (pinfunction "IO8_10") (pintype "bidirectional"))
    )
    (net (code "15") (name "I2C_PW") (class "Default")
      (node (ref "C1") (pin "1") (pinfunction "1_1") (pintype "passive"))
      (node (ref "C2") (pin "1") (pinfunction "1_1") (pintype "passive"))
      (node (ref "R1_PINH") (pin "2") (pinfunction "2_2") (pintype "passive"))
      (node (ref "R2_PINH") (pin "2") (pinfunction "2_2") (pintype "passive"))
      (node (ref "SENSOR2") (pin "2") (pinfunction "CSB_2") (pintype "input"))
      (node (ref "SENSOR2") (pin "6") (pinfunction "VDDIO_6") (pintype "power_in"))
      (node (ref "SENSOR2") (pin "8") (pinfunction "VDD_8") (pintype "power_in"))
      (node (ref "U2") (pin "17") (pinfunction "IO19_17") (pintype "bidirectional"))
    )
    (net (code "16") (name "INT_RTC") (class "Default")
      (node (ref "R1_PINH1") (pin "1") (pinfunction "1_1") (pintype "passive"))
      (node (ref "TP15") (pin "TP") (pinfunction "TP_TP") (pintype "input"))
      (node (ref "U2") (pin "8") (pinfunction "IO0_8") (pintype "bidirectional"))
      (node (ref "U3") (pin "3") (pinfunction "SQW/~{INT}_3") (pintype "output"))
    )
    (net (code "17") (name "IO{slash}BOOT") (class "Default")
      (node (ref "C6") (pin "1") (pinfunction "1_1") (pintype "passive"))
      (node (ref "R_BOOT") (pin "2") (pinfunction "2_2") (pintype "passive"))
      (node (ref "U$2") (pin "3") (pinfunction "3_3") (pintype "passive"))
      (node (ref "U$2") (pin "4") (pinfunction "4_4") (pintype "passive"))
      (node (ref "U2") (pin "15") (pinfunction "IO9_15") (pintype "bidirectional"))
    )
    (net (code "18") (name "IO{slash}CHANGE") (class "Default")
      (node (ref "C10") (pin "1") (pinfunction "1_1") (pintype "passive"))
      (node (ref "R_CHANGE") (pin "2") (pinfunction "2_2") (pintype "passive"))
      (node (ref "U$3") (pin "3") (pinfunction "3_3") (pintype "passive"))
      (node (ref "U$3") (pin "4") (pinfunction "4_4") (pintype "passive"))
      (node (ref "U2") (pin "23") (pinfunction "IO15_23") (pintype "bidirectional"))
    )
    (net (code "19") (name "MISO") (class "Default")
      (node (ref "D12") (pin "1") (pinfunction "1_1") (pintype "passive"))
      (node (ref "J4") (pin "P7") (pinfunction "DAT0_P7") (pintype "bidirectional"))
      (node (ref "R8") (pin "1") (pinfunction "1_1") (pintype "passive"))
      (node (ref "TP6") (pin "TP") (pinfunction "TP_TP") (pintype "input"))
      (node (ref "U1") (pin "2") (pinfunction "DO(IO1)_2") (pintype "bidirectional"))
      (node (ref "U2") (pin "27") (pinfunction "IO2_27") (pintype "bidirectional"))
    )
    (net (code "20") (name "MOSI") (class "Default")
      (node (ref "D11") (pin "1") (pinfunction "1_1") (pintype "passive"))
      (node (ref "J1") (pin "14") (pinfunction "14_14") (pintype "bidirectional"))
      (node (ref "J4") (pin "P3") (pinfunction "CMD_P3") (pintype "bidirectional"))
      (node (ref "R6") (pin "1") (pinfunction "1_1") (pintype "passive"))
      (node (ref "TP7") (pin "TP") (pinfunction "TP_TP") (pintype "input"))
      (node (ref "U1") (pin "5") (pinfunction "DI(IO0)_5") (pintype "bidirectional"))
      (node (ref "U2") (pin "7") (pinfunction "IO7_7") (pintype "bidirectional"))
    )
    (net (code "21") (name "Net-(CHG_LED-PadC)") (class "Default")
      (node (ref "CHG_LED") (pin "C") (pinfunction "C_C") (pintype "passive"))
      (node (ref "R1_BAT") (pin "2") (pinfunction "2_2") (pintype "passive"))
    )
    (net (code "22") (name "Net-(D2-CATHODE)") (class "Default")
      (node (ref "C1_BAT1") (pin "1") (pinfunction "1_1") (pintype "passive"))
      (node (ref "D2") (pin "1") (pinfunction "CATHODE_1") (pintype "bidirectional"))
      (node (ref "IC4") (pin "1") (pinfunction "VIN_1") (pintype "bidirectional"))
      (node (ref "IC4") (pin "3") (pinfunction "CE_3") (pintype "bidirectional"))
      (node (ref "Q1") (pin "2") (pinfunction "S_2") (pintype "bidirectional"))
    )
    (net (code "23") (name "Net-(D3-K)") (class "Default")
      (node (ref "C4") (pin "1") (pinfunction "1_1") (pintype "passive"))
      (node (ref "D3") (pin "1") (pinfunction "K_1") (pintype "bidirectional"))
      (node (ref "D4") (pin "2") (pinfunction "A_2") (pintype "bidirectional"))
    )
    (net (code "24") (name "Net-(D7-CATHODE)") (class "Default")
      (node (ref "D7") (pin "1") (pinfunction "CATHODE_1") (pintype "bidirectional"))
      (node (ref "R_CAPACITOR") (pin "2") (pinfunction "2_2") (pintype "passive"))
    )
    (net (code "25") (name "Net-(EPD_C1-Pad1)") (class "Default")
      (node (ref "EPD_C1") (pin "1") (pinfunction "1_1") (pintype "passive"))
      (node (ref "J1") (pin "4") (pinfunction "4_4") (pintype "bidirectional"))
    )
    (net (code "26") (name "Net-(EPD_C2-Pad1)") (class "Default")
      (node (ref "EPD_C2") (pin "1") (pinfunction "1_1") (pintype "passive"))
      (node (ref "J1") (pin "5") (pinfunction "5_5") (pintype "bidirectional"))
    )
    (net (code "27") (name "Net-(EPD_C6-Pad1)") (class "Default")
      (node (ref "EPD_C6") (pin "1") (pinfunction "1_1") (pintype "passive"))
      (node (ref "J1") (pin "18") (pinfunction "18_18") (pintype "bidirectional"))
    )
    (net (code "28") (name "Net-(EPD_C7-Pad1)") (class "Default")
      (node (ref "EPD_C7") (pin "1") (pinfunction "1_1") (pintype "passive"))
      (node (ref "J1") (pin "19") (pinfunction "19_19") (pintype "bidirectional"))
    )
    (net (code "29") (name "Net-(EPD_C8-Pad1)") (class "Default")
      (node (ref "EPD_C8") (pin "1") (pinfunction "1_1") (pintype "passive"))
      (node (ref "J1") (pin "20") (pinfunction "20_20") (pintype "bidirectional"))
    )
    (net (code "30") (name "Net-(EPD_C9-Pad1)") (class "Default")
      (node (ref "EPD_C9") (pin "1") (pinfunction "1_1") (pintype "passive"))
      (node (ref "J1") (pin "21") (pinfunction "21_21") (pintype "bidirectional"))
    )
    (net (code "31") (name "Net-(EPD_C10-Pad1)") (class "Default")
      (node (ref "EPD_C10") (pin "1") (pinfunction "1_1") (pintype "passive"))
      (node (ref "J1") (pin "22") (pinfunction "22_22") (pintype "bidirectional"))
    )
    (net (code "32") (name "Net-(EPD_C11-Pad1)") (class "Default")
      (node (ref "EPD_C11") (pin "1") (pinfunction "1_1") (pintype "passive"))
      (node (ref "J1") (pin "23") (pinfunction "23_23") (pintype "bidirectional"))
    )
    (net (code "33") (name "Net-(EPD_C12-Pad1)") (class "Default")
      (node (ref "EPD_C12") (pin "1") (pinfunction "1_1") (pintype "passive"))
      (node (ref "J1") (pin "24") (pinfunction "24_24") (pintype "bidirectional"))
    )
    (net (code "34") (name "Net-(IC1-CT)") (class "Default")
      (node (ref "C_DELAY") (pin "1") (pinfunction "1_1") (pintype "passive"))
      (node (ref "IC1") (pin "5") (pinfunction "CT_5") (pintype "bidirectional"))
    )
    (net (code "35") (name "Net-(J2-PadA5)") (class "Default")
      (node (ref "J2") (pin "A5") (pinfunction "A5_A5") (pintype "bidirectional"))
      (node (ref "R2-USB1") (pin "2") (pinfunction "2_2") (pintype "passive"))
    )
    (net (code "36") (name "Net-(J2-PadB5)") (class "Default")
      (node (ref "J2") (pin "B5") (pinfunction "B5_B5") (pintype "bidirectional"))
      (node (ref "R2-USB") (pin "1") (pinfunction "1_1") (pintype "passive"))
    )
    (net (code "37") (name "Net-(MCP73831-PROG)") (class "Default")
      (node (ref "MCP73831") (pin "5") (pinfunction "PROG_5") (pintype "input"))
      (node (ref "R2_BAT") (pin "2") (pinfunction "2_2") (pintype "passive"))
    )
    (net (code "38") (name "Net-(MCP73831-STAT)") (class "Default")
      (node (ref "MCP73831") (pin "1") (pinfunction "STAT_1") (pintype "output"))
      (node (ref "R1_BAT") (pin "1") (pinfunction "1_1") (pintype "passive"))
    )
    (net (code "39") (name "PREVGH") (class "Default")
      (node (ref "D5") (pin "1") (pinfunction "K_1") (pintype "bidirectional"))
    )
    (net (code "40") (name "PREVGL") (class "Default")
      (node (ref "D3") (pin "2") (pinfunction "A_2") (pintype "bidirectional"))
    )
    (net (code "41") (name "RESE") (class "Default")
      (node (ref "J1") (pin "3") (pinfunction "3_3") (pintype "bidirectional"))
      (node (ref "Q3") (pin "2") (pinfunction "S_2") (pintype "bidirectional"))
      (node (ref "R3") (pin "2") (pinfunction "2_2") (pintype "passive"))
    )
    (net (code "42") (name "RESE'") (class "Default")
      (node (ref "R2") (pin "2") (pinfunction "2_2") (pintype "passive"))
      (node (ref "R3") (pin "1") (pinfunction "1_1") (pintype "passive"))
      (node (ref "SJ1") (pin "2") (pinfunction "2_2") (pintype "passive"))
    )
    (net (code "43") (name "RESET") (class "Default")
      (node (ref "C5") (pin "1") (pinfunction "1_1") (pintype "passive"))
      (node (ref "IC1") (pin "1") (pinfunction "VOUT_1") (pintype "bidirectional"))
      (node (ref "R_RESET") (pin "2") (pinfunction "2_2") (pintype "passive"))
      (node (ref "U$1") (pin "4") (pinfunction "4_4") (pintype "passive"))
      (node (ref "U2") (pin "3") (pinfunction "EN_3") (pintype "input"))
    )
    (net (code "44") (name "RTC_RST") (class "Default")
      (node (ref "U2") (pin "16") (pinfunction "IO18_16") (pintype "bidirectional"))
      (node (ref "U3") (pin "4") (pinfunction "~{RST}_4") (pintype "input"))
    )
    (net (code "45") (name "RX") (class "Default")
      (node (ref "TP2") (pin "TP") (pinfunction "TP_TP") (pintype "input"))
      (node (ref "U2") (pin "24") (pinfunction "RXD0/GPIO17_24") (pintype "bidirectional"))
    )
    (net (code "46") (name "SCK") (class "Default")
      (node (ref "D10") (pin "1") (pinfunction "1_1") (pintype "passive"))
      (node (ref "J1") (pin "13") (pinfunction "13_13") (pintype "bidirectional"))
      (node (ref "J4") (pin "P5") (pinfunction "CLK_P5") (pintype "bidirectional"))
      (node (ref "R7") (pin "1") (pinfunction "1_1") (pintype "passive"))
      (node (ref "TP8") (pin "TP") (pinfunction "TP_TP") (pintype "input"))
      (node (ref "U1") (pin "6") (pinfunction "CLK_6") (pintype "input"))
      (node (ref "U2") (pin "6") (pinfunction "IO6_6") (pintype "bidirectional"))
    )
    (net (code "47") (name "SCL") (class "Default")
      (node (ref "J3") (pin "4") (pinfunction "4_4") (pintype "passive"))
      (node (ref "R2_PINH") (pin "1") (pinfunction "1_1") (pintype "passive"))
      (node (ref "SENSOR2") (pin "4") (pinfunction "SCK_4") (pintype "input"))
      (node (ref "U2") (pin "20") (pinfunction "IO22_20") (pintype "bidirectional"))
      (node (ref "U3") (pin "16") (pinfunction "SCL_16") (pintype "input"))
      (node (ref "U4") (pin "7") (pinfunction "SCL_7") (pintype "input"))
    )
    (net (code "48") (name "SDA") (class "Default")
      (node (ref "J3") (pin "3") (pinfunction "3_3") (pintype "passive"))
      (node (ref "R1_PINH") (pin "1") (pinfunction "1_1") (pintype "passive"))
      (node (ref "SENSOR2") (pin "3") (pinfunction "SDI_3") (pintype "bidirectional"))
      (node (ref "U2") (pin "19") (pinfunction "IO21_19") (pintype "bidirectional"))
      (node (ref "U3") (pin "15") (pinfunction "SDA_15") (pintype "bidirectional"))
      (node (ref "U4") (pin "8") (pinfunction "SDA_8") (pintype "bidirectional"))
    )
    (net (code "49") (name "SRC") (class "Default")
      (node (ref "C4") (pin "2") (pinfunction "2_2") (pintype "passive"))
      (node (ref "D5") (pin "2") (pinfunction "A_2") (pintype "bidirectional"))
      (node (ref "L1") (pin "1") (pinfunction "1_1") (pintype "passive"))
      (node (ref "Q3") (pin "3") (pinfunction "D_3") (pintype "bidirectional"))
    )
    (net (code "50") (name "SS_SD") (class "Default")
      (node (ref "D6") (pin "1") (pinfunction "1_1") (pintype "passive"))
      (node (ref "J4") (pin "P2") (pinfunction "CD/DAT3_P2") (pintype "bidirectional"))
      (node (ref "R10") (pin "1") (pinfunction "1_1") (pintype "passive"))
      (node (ref "U2") (pin "4") (pinfunction "IO4_4") (pintype "bidirectional"))
    )
    (net (code "51") (name "TX") (class "Default")
      (node (ref "TP1") (pin "TP") (pinfunction "TP_TP") (pintype "input"))
      (node (ref "U2") (pin "25") (pinfunction "TXD0/GPIO16_25") (pintype "bidirectional"))
    )
    (net (code "52") (name "USB_D+") (class "Default")
      (node (ref "D1") (pin "1") (pinfunction "I/O1_1_1") (pintype "bidirectional"))
      (node (ref "U2") (pin "14") (pinfunction "IO13_14") (pintype "bidirectional"))
    )
    (net (code "53") (name "USB_D-") (class "Default")
      (node (ref "D1") (pin "3") (pinfunction "I/O2_1_3") (pintype "bidirectional"))
      (node (ref "U2") (pin "13") (pinfunction "IO12_13") (pintype "bidirectional"))
    )
    (net (code "54") (name "VBAT") (class "Default")
      (node (ref "C2_BAT") (pin "1") (pinfunction "1_1") (pintype "passive"))
      (node (ref "MCP73831") (pin "3") (pinfunction "VBAT_3") (pintype "power_in"))
      (node (ref "Q1") (pin "3") (pinfunction "D_3") (pintype "bidirectional"))
      (node (ref "TP3") (pin "TP") (pinfunction "TP_TP") (pintype "input"))
      (node (ref "U4") (pin "2") (pinfunction "CELL_2") (pintype "power_in"))
      (node (ref "U4") (pin "3") (pinfunction "VDD_3") (pintype "power_in"))
    )
    (net (code "55") (name "VBUS") (class "Default")
      (node (ref "C1_BAT") (pin "1") (pinfunction "1_1") (pintype "passive"))
      (node (ref "C4_USB") (pin "1") (pinfunction "1_1") (pintype "passive"))
      (node (ref "C5_USB") (pin "1") (pinfunction "1_1") (pintype "passive"))
      (node (ref "CHG_LED") (pin "A") (pinfunction "A_A") (pintype "passive"))
      (node (ref "D1") (pin "5") (pinfunction "VBUS_5") (pintype "bidirectional"))
      (node (ref "D2") (pin "2") (pinfunction "ANODE_2") (pintype "bidirectional"))
      (node (ref "MCP73831") (pin "4") (pinfunction "VIN_4") (pintype "power_in"))
      (node (ref "PFMF.050.1") (pin "2") (pinfunction "2_2") (pintype "passive"))
      (node (ref "Q1") (pin "1") (pinfunction "G_1") (pintype "bidirectional"))
      (node (ref "R1_PWRUSB") (pin "1") (pinfunction "1_1") (pintype "passive"))
      (node (ref "TP14") (pin "TP") (pinfunction "TP_TP") (pintype "input"))
    )
    (net (code "56") (name "VRTC") (class "Default")
      (node (ref "C10_SUPERCAP") (pin "2") (pinfunction "2_2") (pintype "passive"))
      (node (ref "C8") (pin "1") (pinfunction "1_1") (pintype "passive"))
      (node (ref "R_CAPACITOR") (pin "1") (pinfunction "1_1") (pintype "passive"))
      (node (ref "U3") (pin "14") (pinfunction "VBAT_14") (pintype "power_in"))
    )
    (net (code "57") (name "VUSB") (class "Default")
      (node (ref "J2") (pin "A4") (pinfunction "A4_A4") (pintype "bidirectional"))
      (node (ref "J2") (pin "A9") (pinfunction "A9_A9") (pintype "bidirectional"))
      (node (ref "J2") (pin "B4") (pinfunction "B4_B4") (pintype "bidirectional"))
      (node (ref "J2") (pin "B9") (pinfunction "B9_B9") (pintype "bidirectional"))
      (node (ref "PFMF.050.1") (pin "1") (pinfunction "1_1") (pintype "passive"))
    )
    (net (code "58") (name "unconnected-(IC1-NC-Pad4)") (class "Default")
      (node (ref "IC1") (pin "4") (pinfunction "NC_4") (pintype "no_connect"))
    )
    (net (code "59") (name "unconnected-(IC4-NC-Pad4)") (class "Default")
      (node (ref "IC4") (pin "4") (pinfunction "NC_4") (pintype "no_connect"))
    )
    (net (code "60") (name "unconnected-(J1-Pad1)") (class "Default")
      (node (ref "J1") (pin "1") (pinfunction "1_1") (pintype "bidirectional"))
    )
    (net (code "61") (name "unconnected-(J1-Pad6)") (class "Default")
      (node (ref "J1") (pin "6") (pinfunction "6_6") (pintype "bidirectional"))
    )
    (net (code "62") (name "unconnected-(J1-Pad7)") (class "Default")
      (node (ref "J1") (pin "7") (pinfunction "7_7") (pintype "bidirectional"))
    )
    (net (code "63") (name "unconnected-(J2-PadA8)") (class "Default")
      (node (ref "J2") (pin "A8") (pinfunction "A8_A8") (pintype "bidirectional"))
    )
    (net (code "64") (name "unconnected-(J2-PadB8)") (class "Default")
      (node (ref "J2") (pin "B8") (pinfunction "B8_B8") (pintype "bidirectional"))
    )
    (net (code "65") (name "unconnected-(J4-DAT1-PadP8)") (class "Default")
      (node (ref "J4") (pin "P8") (pinfunction "DAT1_P8") (pintype "bidirectional"))
    )
    (net (code "66") (name "unconnected-(J4-DAT2-PadP1)") (class "Default")
      (node (ref "J4") (pin "P1") (pinfunction "DAT2_P1") (pintype "bidirectional"))
    )
    (net (code "67") (name "unconnected-(J4-DETECTION_1-PadS1)") (class "Default")
      (node (ref "J4") (pin "S1") (pinfunction "DETECTION_1_S1") (pintype "bidirectional"))
    )
    (net (code "68") (name "unconnected-(J4-DETECTION_2-PadS2)") (class "Default")
      (node (ref "J4") (pin "S2") (pinfunction "DETECTION_2_S2") (pintype "bidirectional"))
    )
    (net (code "69") (name "unconnected-(U$1-Pad3)") (class "Default")
      (node (ref "U$1") (pin "3") (pinfunction "3_3") (pintype "passive"))
    )
    (net (code "70") (name "unconnected-(U2-NC-Pad22)") (class "Default")
      (node (ref "U2") (pin "22") (pinfunction "NC_22") (pintype "no_connect"))
    )
    (net (code "71") (name "unconnected-(U4-~{ALERT}-Pad5)") (class "Default")
      (node (ref "U4") (pin "5") (pinfunction "~{ALERT}_5") (pintype "output"))
    )
  )
)
